# main.net
KiCad netlist of a schematic drawn in Altium Designer
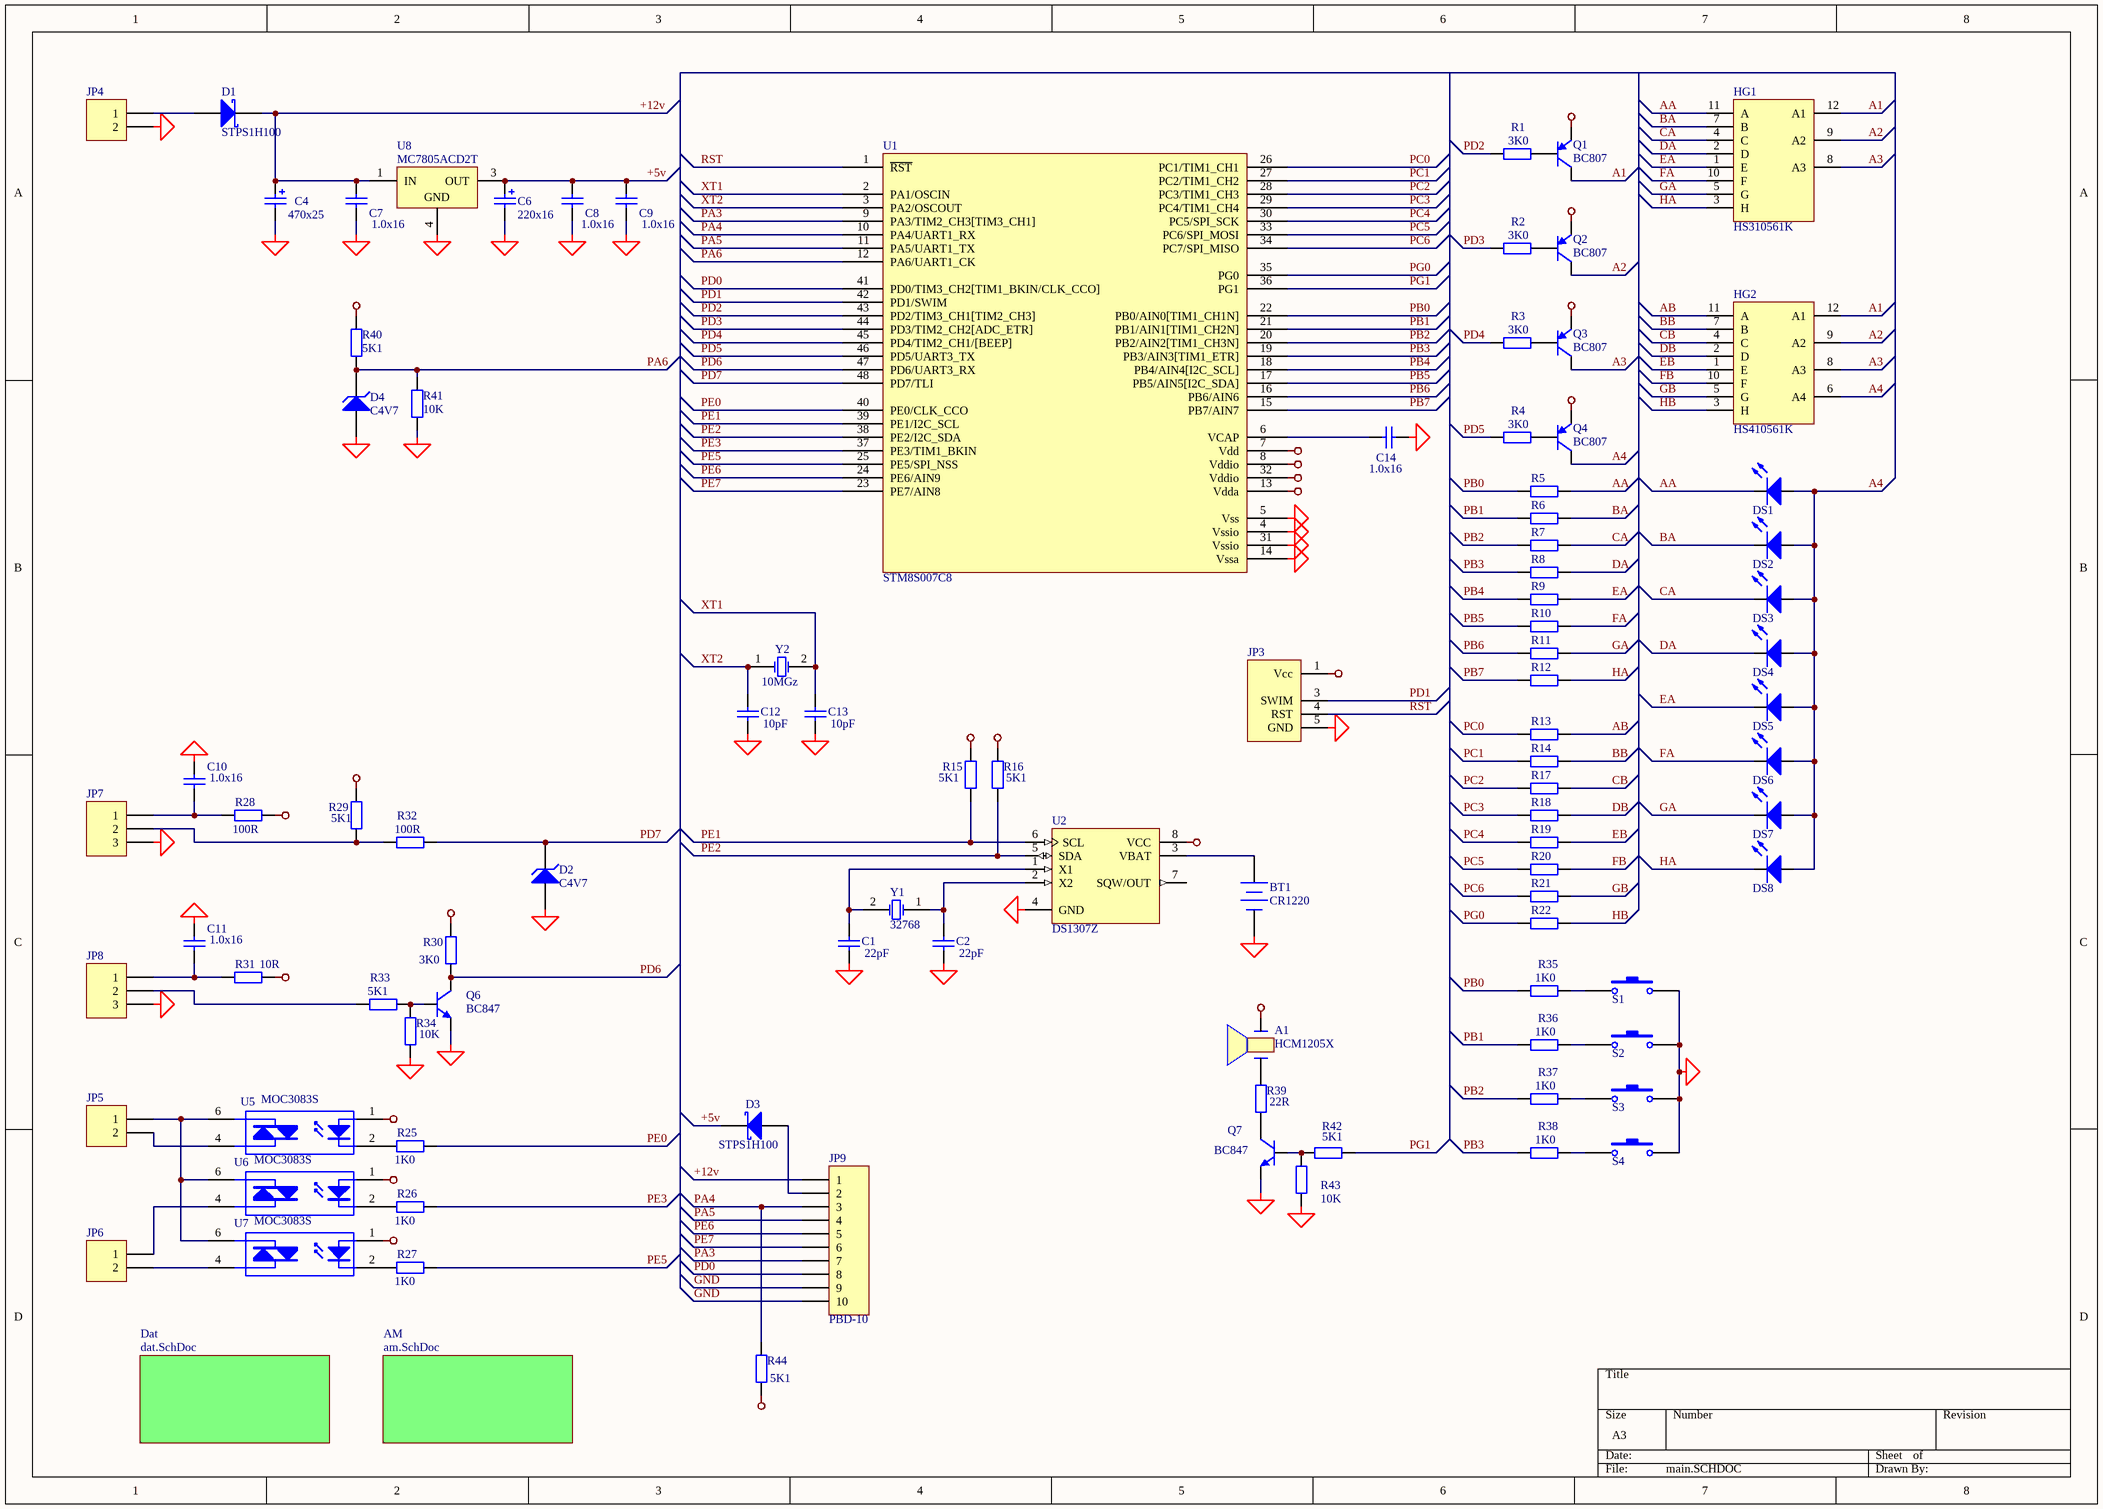
[diagram p0: main.SCHDOC]

(export (version "E")
  (design (tool "Eeschema 10.0.6"))
  (components
    (comp (ref "A1")
      (value "HCM1205X")
      (footprint "zumm")
      (description "Beeper")
      (libsource (lib "PAL") (part "PJEZ0"))
    )
    (comp (ref "BT1")
      (value "CR1220")
      (footprint "1220_holder")
      (description "Multicell Battery")
      (fields (field (name "MANUFACTURER") "Generic Components") (field (name "PUBLISHER") "Altium Limited"))
      (libsource (lib "Miscellaneous Devices") (part "Battery"))
    )
    (comp (ref "C1")
      (value "22pF")
      (footprint "_1206")
      (description "Capacitor")
      (fields (field (name "MANUFACTURER") "Generic Components") (field (name "PUBLISHER") "Altium Limited"))
      (libsource (lib "Miscellaneous Devices") (part "Cap Semi"))
    )
    (comp (ref "C2")
      (value "22pF")
      (footprint "_1206")
      (description "Capacitor")
      (fields (field (name "MANUFACTURER") "Generic Components") (field (name "PUBLISHER") "Altium Limited"))
      (libsource (lib "Miscellaneous Devices") (part "Cap Semi"))
    )
    (comp (ref "C4")
      (value "470x25")
      (footprint "el5")
      (description "Polarized Capacitor (Radial)")
      (fields (field (name "MANUFACTURER") "Generic Components") (field (name "PUBLISHER") "Altium Limited"))
      (libsource (lib "BUF") (part "Cap Pol1"))
    )
    (comp (ref "C6")
      (value "220x16")
      (footprint "el3")
      (description "Polarized Capacitor (Radial)")
      (fields (field (name "MANUFACTURER") "Generic Components") (field (name "PUBLISHER") "Altium Limited"))
      (libsource (lib "BUF") (part "Cap Pol"))
    )
    (comp (ref "C7")
      (value "1.0x16")
      (footprint "_1206")
      (description "Capacitor")
      (fields (field (name "MANUFACTURER") "Generic Components") (field (name "PUBLISHER") "Altium Limited"))
      (libsource (lib "BUF") (part "Cap"))
    )
    (comp (ref "C8")
      (value "1.0x16")
      (footprint "_1206")
      (description "Capacitor")
      (fields (field (name "MANUFACTURER") "Generic Components") (field (name "PUBLISHER") "Altium Limited"))
      (libsource (lib "BUF") (part "Cap"))
    )
    (comp (ref "C9")
      (value "1.0x16")
      (footprint "_1206")
      (description "Capacitor")
      (fields (field (name "MANUFACTURER") "Generic Components") (field (name "PUBLISHER") "Altium Limited"))
      (libsource (lib "BUF") (part "Cap"))
    )
    (comp (ref "C10")
      (value "1.0x16")
      (footprint "_1206")
      (description "Capacitor")
      (fields (field (name "MANUFACTURER") "Generic Components") (field (name "PUBLISHER") "Altium Limited"))
      (libsource (lib "BUF") (part "Cap"))
    )
    (comp (ref "C11")
      (value "1.0x16")
      (footprint "_1206")
      (description "Capacitor")
      (fields (field (name "MANUFACTURER") "Generic Components") (field (name "PUBLISHER") "Altium Limited"))
      (libsource (lib "BUF") (part "Cap"))
    )
    (comp (ref "C12")
      (value "10pF")
      (footprint "_1206")
      (description "Capacitor")
      (fields (field (name "MANUFACTURER") "Generic Components") (field (name "PUBLISHER") "Altium Limited"))
      (libsource (lib "Miscellaneous Devices") (part "Cap Semi"))
    )
    (comp (ref "C13")
      (value "10pF")
      (footprint "_1206")
      (description "Capacitor")
      (fields (field (name "MANUFACTURER") "Generic Components") (field (name "PUBLISHER") "Altium Limited"))
      (libsource (lib "Miscellaneous Devices") (part "Cap Semi"))
    )
    (comp (ref "C14")
      (value "1.0x16")
      (footprint "_1206")
      (description "Capacitor")
      (fields (field (name "MANUFACTURER") "Generic Components") (field (name "PUBLISHER") "Altium Limited"))
      (libsource (lib "Miscellaneous Devices") (part "Cap Semi"))
    )
    (comp (ref "D1")
      (value "STPS1H100")
      (footprint "mbrs140")
      (description "Schottky Rectifier")
      (fields
        (field (name "MANUFACTURER") "International Rectifier")
        (field (name "PUBLISHER") "Altium Limited")
      )
      (libsource (lib "IR Discrete Diode") (part "10BQ015"))
    )
    (comp (ref "D2")
      (value "C4V7")
      (footprint "_1206d")
      (description "Zener Diode")
      (fields (field (name "MANUFACTURER") "Generic Components") (field (name "PUBLISHER") "Altium Limited"))
      (libsource (lib "Miscellaneous Devices") (part "D Zener"))
    )
    (comp (ref "D3")
      (value "STPS1H100")
      (footprint "MBRS140")
      (description "Schottky Rectifier")
      (fields
        (field (name "MANUFACTURER") "International Rectifier")
        (field (name "PUBLISHER") "Altium Limited")
      )
      (libsource (lib "IR Discrete Diode") (part "10BQ015"))
    )
    (comp (ref "D4")
      (value "C4V7")
      (footprint "_1206d")
      (description "Zener Diode")
      (fields (field (name "MANUFACTURER") "Generic Components") (field (name "PUBLISHER") "Altium Limited"))
      (libsource (lib "Miscellaneous Devices") (part "D Zener"))
    )
    (comp (ref "DS1")
      (value "LED0")
      (footprint "el3")
      (description "Typical INFRARED GaAs LED")
      (fields (field (name "MANUFACTURER") "Generic Components") (field (name "PUBLISHER") "Altium Limited"))
      (libsource (lib "PAL") (part "LED0"))
    )
    (comp (ref "DS2")
      (value "LED0")
      (footprint "el3")
      (description "Typical INFRARED GaAs LED")
      (fields (field (name "MANUFACTURER") "Generic Components") (field (name "PUBLISHER") "Altium Limited"))
      (libsource (lib "PAL") (part "LED0"))
    )
    (comp (ref "DS3")
      (value "LED0")
      (footprint "el3")
      (description "Typical INFRARED GaAs LED")
      (fields (field (name "MANUFACTURER") "Generic Components") (field (name "PUBLISHER") "Altium Limited"))
      (libsource (lib "PAL") (part "LED0"))
    )
    (comp (ref "DS4")
      (value "LED0")
      (footprint "el3")
      (description "Typical INFRARED GaAs LED")
      (fields (field (name "MANUFACTURER") "Generic Components") (field (name "PUBLISHER") "Altium Limited"))
      (libsource (lib "PAL") (part "LED0"))
    )
    (comp (ref "DS5")
      (value "LED0")
      (footprint "el3")
      (description "Typical INFRARED GaAs LED")
      (fields (field (name "MANUFACTURER") "Generic Components") (field (name "PUBLISHER") "Altium Limited"))
      (libsource (lib "PAL") (part "LED0"))
    )
    (comp (ref "DS6")
      (value "LED0")
      (footprint "el3")
      (description "Typical INFRARED GaAs LED")
      (fields (field (name "MANUFACTURER") "Generic Components") (field (name "PUBLISHER") "Altium Limited"))
      (libsource (lib "PAL") (part "LED0"))
    )
    (comp (ref "DS7")
      (value "LED0")
      (footprint "el3")
      (description "Typical INFRARED GaAs LED")
      (fields (field (name "MANUFACTURER") "Generic Components") (field (name "PUBLISHER") "Altium Limited"))
      (libsource (lib "PAL") (part "LED0"))
    )
    (comp (ref "DS8")
      (value "LED0")
      (footprint "el3")
      (description "Typical INFRARED GaAs LED")
      (fields (field (name "MANUFACTURER") "Generic Components") (field (name "PUBLISHER") "Altium Limited"))
      (libsource (lib "PAL") (part "LED0"))
    )
    (comp (ref "HG1") (value "HS310561K") (footprint "HS310561K") (libsource (lib "PAL") (part "HS310561K")))
    (comp (ref "HG2") (value "HS410561K") (footprint "HS410561K") (libsource (lib "PAL") (part "HS410561K")))
    (comp (ref "JP3") (value "~") (footprint "HDR1X5_uart") (libsource (lib "PAL") (part "SWIM_CONN")))
    (comp (ref "JP4")
      (value "DG306-5.0-02P")
      (footprint "BT5-2")
      (description "Header, 2-Pin")
      (fields (field (name "MANUFACTURER") "Generic Components") (field (name "PUBLISHER") "Altium Limited"))
      (libsource (lib "Miscellaneous Connectors") (part "Header 2"))
    )
    (comp (ref "JP5")
      (value "DG306-5.0-02P")
      (footprint "BT5-2")
      (description "Header, 2-Pin")
      (fields (field (name "MANUFACTURER") "Generic Components") (field (name "PUBLISHER") "Altium Limited"))
      (libsource (lib "Miscellaneous Connectors") (part "Header 2"))
    )
    (comp (ref "JP6")
      (value "DG306-5.0-02P")
      (footprint "BT5-2")
      (description "Header, 2-Pin")
      (fields (field (name "MANUFACTURER") "Generic Components") (field (name "PUBLISHER") "Altium Limited"))
      (libsource (lib "Miscellaneous Connectors") (part "Header 2"))
    )
    (comp (ref "JP7")
      (value "DG306-5.0-03P")
      (footprint "BT5-3")
      (description "Header, 3-Pin")
      (fields (field (name "MANUFACTURER") "Generic Components") (field (name "PUBLISHER") "Altium Limited"))
      (libsource (lib "Miscellaneous Connectors") (part "Header 3"))
    )
    (comp (ref "JP8")
      (value "DG306-5.0-03P")
      (footprint "BT5-3")
      (description "Header, 3-Pin")
      (fields (field (name "MANUFACTURER") "Generic Components") (field (name "PUBLISHER") "Altium Limited"))
      (libsource (lib "Miscellaneous Connectors") (part "Header 3"))
    )
    (comp (ref "JP9")
      (value "PBD-10")
      (footprint "HDR2X5")
      (description "Header, 10-Pin")
      (fields (field (name "MANUFACTURER") "Generic Components") (field (name "PUBLISHER") "Altium Limited"))
      (libsource (lib "Miscellaneous Connectors") (part "Header 10"))
    )
    (comp (ref "Q1")
      (value "BC807")
      (footprint "SO-G3")
      (description "General Purpose Transistor PNP Silicon")
      (fields (field (name "MANUFACTURER") "Motorola") (field (name "PUBLISHER") "Altium Limited"))
      (libsource (lib "PAL") (part "BC857ALT1"))
    )
    (comp (ref "Q2")
      (value "BC807")
      (footprint "SO-G3")
      (description "General Purpose Transistor PNP Silicon")
      (fields (field (name "MANUFACTURER") "Motorola") (field (name "PUBLISHER") "Altium Limited"))
      (libsource (lib "PAL") (part "BC857ALT1"))
    )
    (comp (ref "Q3")
      (value "BC807")
      (footprint "SO-G3")
      (description "General Purpose Transistor PNP Silicon")
      (fields (field (name "MANUFACTURER") "Motorola") (field (name "PUBLISHER") "Altium Limited"))
      (libsource (lib "PAL") (part "BC857ALT1"))
    )
    (comp (ref "Q4")
      (value "BC807")
      (footprint "SO-G3")
      (description "General Purpose Transistor PNP Silicon")
      (fields (field (name "MANUFACTURER") "Motorola") (field (name "PUBLISHER") "Altium Limited"))
      (libsource (lib "PAL") (part "BC857ALT1"))
    )
    (comp (ref "Q6")
      (value "BC847")
      (footprint "SO-G3")
      (description "General Purpose Transistor NPN Silicon")
      (fields (field (name "MANUFACTURER") "Motorola") (field (name "PUBLISHER") "Altium Limited"))
      (libsource (lib "PAL") (part "BC847ALT1"))
    )
    (comp (ref "Q7")
      (value "BC847")
      (footprint "SO-G3")
      (description "General Purpose Transistor NPN Silicon")
      (fields (field (name "MANUFACTURER") "Motorola") (field (name "PUBLISHER") "Altium Limited"))
      (libsource (lib "PAL") (part "BC847ALT1"))
    )
    (comp (ref "R1")
      (value "3K0")
      (footprint "_1206")
      (description "Resistor")
      (fields (field (name "MANUFACTURER") "Generic Components") (field (name "PUBLISHER") "Altium Limited"))
      (libsource (lib "") (part "Res2_1"))
    )
    (comp (ref "R2")
      (value "3K0")
      (footprint "_1206")
      (description "Resistor")
      (fields (field (name "MANUFACTURER") "Generic Components") (field (name "PUBLISHER") "Altium Limited"))
      (libsource (lib "") (part "Res2_1"))
    )
    (comp (ref "R3")
      (value "3K0")
      (footprint "_1206")
      (description "Resistor")
      (fields (field (name "MANUFACTURER") "Generic Components") (field (name "PUBLISHER") "Altium Limited"))
      (libsource (lib "") (part "Res2_1"))
    )
    (comp (ref "R4")
      (value "3K0")
      (footprint "_1206")
      (description "Resistor")
      (fields (field (name "MANUFACTURER") "Generic Components") (field (name "PUBLISHER") "Altium Limited"))
      (libsource (lib "") (part "Res2_1"))
    )
    (comp (ref "R5")
      (value "100R")
      (footprint "_1206")
      (description "Resistor")
      (fields (field (name "MANUFACTURER") "Generic Components") (field (name "PUBLISHER") "Altium Limited"))
      (libsource (lib "") (part "Res2_1"))
    )
    (comp (ref "R6")
      (value "100R")
      (footprint "_1206")
      (description "Resistor")
      (fields (field (name "MANUFACTURER") "Generic Components") (field (name "PUBLISHER") "Altium Limited"))
      (libsource (lib "") (part "Res2_1"))
    )
    (comp (ref "R7")
      (value "100R")
      (footprint "_1206")
      (description "Resistor")
      (fields (field (name "MANUFACTURER") "Generic Components") (field (name "PUBLISHER") "Altium Limited"))
      (libsource (lib "") (part "Res2_1"))
    )
    (comp (ref "R8")
      (value "100R")
      (footprint "_1206")
      (description "Resistor")
      (fields (field (name "MANUFACTURER") "Generic Components") (field (name "PUBLISHER") "Altium Limited"))
      (libsource (lib "") (part "Res2_1"))
    )
    (comp (ref "R9")
      (value "100R")
      (footprint "_1206")
      (description "Resistor")
      (fields (field (name "MANUFACTURER") "Generic Components") (field (name "PUBLISHER") "Altium Limited"))
      (libsource (lib "") (part "Res2_1"))
    )
    (comp (ref "R10")
      (value "100R")
      (footprint "_1206")
      (description "Resistor")
      (fields (field (name "MANUFACTURER") "Generic Components") (field (name "PUBLISHER") "Altium Limited"))
      (libsource (lib "") (part "Res2_1"))
    )
    (comp (ref "R11")
      (value "100R")
      (footprint "_1206")
      (description "Resistor")
      (fields (field (name "MANUFACTURER") "Generic Components") (field (name "PUBLISHER") "Altium Limited"))
      (libsource (lib "") (part "Res2_1"))
    )
    (comp (ref "R12")
      (value "100R")
      (footprint "_1206")
      (description "Resistor")
      (fields (field (name "MANUFACTURER") "Generic Components") (field (name "PUBLISHER") "Altium Limited"))
      (libsource (lib "") (part "Res2_1"))
    )
    (comp (ref "R13")
      (value "100R")
      (footprint "_1206")
      (description "Resistor")
      (fields (field (name "MANUFACTURER") "Generic Components") (field (name "PUBLISHER") "Altium Limited"))
      (libsource (lib "") (part "Res2_1"))
    )
    (comp (ref "R14")
      (value "100R")
      (footprint "_1206")
      (description "Resistor")
      (fields (field (name "MANUFACTURER") "Generic Components") (field (name "PUBLISHER") "Altium Limited"))
      (libsource (lib "") (part "Res2_1"))
    )
    (comp (ref "R15")
      (value "5K1")
      (footprint "_1206")
      (description "Resistor")
      (fields (field (name "MANUFACTURER") "Generic Components") (field (name "PUBLISHER") "Altium Limited"))
      (libsource (lib "Miscellaneous Devices") (part "Res2"))
    )
    (comp (ref "R16")
      (value "5K1")
      (footprint "_1206")
      (description "Resistor")
      (fields (field (name "MANUFACTURER") "Generic Components") (field (name "PUBLISHER") "Altium Limited"))
      (libsource (lib "Miscellaneous Devices") (part "Res2"))
    )
    (comp (ref "R17")
      (value "100R")
      (footprint "_1206")
      (description "Resistor")
      (fields (field (name "MANUFACTURER") "Generic Components") (field (name "PUBLISHER") "Altium Limited"))
      (libsource (lib "") (part "Res2_1"))
    )
    (comp (ref "R18")
      (value "100R")
      (footprint "_1206")
      (description "Resistor")
      (fields (field (name "MANUFACTURER") "Generic Components") (field (name "PUBLISHER") "Altium Limited"))
      (libsource (lib "") (part "Res2_1"))
    )
    (comp (ref "R19")
      (value "100R")
      (footprint "_1206")
      (description "Resistor")
      (fields (field (name "MANUFACTURER") "Generic Components") (field (name "PUBLISHER") "Altium Limited"))
      (libsource (lib "") (part "Res2_1"))
    )
    (comp (ref "R20")
      (value "100R")
      (footprint "_1206")
      (description "Resistor")
      (fields (field (name "MANUFACTURER") "Generic Components") (field (name "PUBLISHER") "Altium Limited"))
      (libsource (lib "") (part "Res2_1"))
    )
    (comp (ref "R21")
      (value "100R")
      (footprint "_1206")
      (description "Resistor")
      (fields (field (name "MANUFACTURER") "Generic Components") (field (name "PUBLISHER") "Altium Limited"))
      (libsource (lib "") (part "Res2_1"))
    )
    (comp (ref "R22")
      (value "100R")
      (footprint "_1206")
      (description "Resistor")
      (fields (field (name "MANUFACTURER") "Generic Components") (field (name "PUBLISHER") "Altium Limited"))
      (libsource (lib "") (part "Res2_1"))
    )
    (comp (ref "R25")
      (value "1K0")
      (footprint "_1206")
      (description "Resistor")
      (fields (field (name "MANUFACTURER") "Generic Components") (field (name "PUBLISHER") "Altium Limited"))
      (libsource (lib "") (part "Res2_3"))
    )
    (comp (ref "R26")
      (value "1K0")
      (footprint "_1206")
      (description "Resistor")
      (fields (field (name "MANUFACTURER") "Generic Components") (field (name "PUBLISHER") "Altium Limited"))
      (libsource (lib "") (part "Res2_3"))
    )
    (comp (ref "R27")
      (value "1K0")
      (footprint "_1206")
      (description "Resistor")
      (fields (field (name "MANUFACTURER") "Generic Components") (field (name "PUBLISHER") "Altium Limited"))
      (libsource (lib "") (part "Res2_3"))
    )
    (comp (ref "R28")
      (value "100R")
      (footprint "_1206")
      (description "Resistor")
      (fields (field (name "MANUFACTURER") "Generic Components") (field (name "PUBLISHER") "Altium Limited"))
      (libsource (lib "") (part "Res2_3"))
    )
    (comp (ref "R29")
      (value "5K1")
      (footprint "_1206")
      (description "Resistor")
      (fields (field (name "MANUFACTURER") "Generic Components") (field (name "PUBLISHER") "Altium Limited"))
      (libsource (lib "Miscellaneous Devices") (part "Res2"))
    )
    (comp (ref "R30")
      (value "3K0")
      (footprint "_1206")
      (description "Resistor")
      (fields (field (name "MANUFACTURER") "Generic Components") (field (name "PUBLISHER") "Altium Limited"))
      (libsource (lib "Miscellaneous Devices") (part "Res2"))
    )
    (comp (ref "R31")
      (value "10R")
      (footprint "_1206")
      (description "Resistor")
      (fields (field (name "MANUFACTURER") "Generic Components") (field (name "PUBLISHER") "Altium Limited"))
      (libsource (lib "") (part "Res2_3"))
    )
    (comp (ref "R32")
      (value "100R")
      (footprint "_1206")
      (description "Resistor")
      (fields (field (name "MANUFACTURER") "Generic Components") (field (name "PUBLISHER") "Altium Limited"))
      (libsource (lib "") (part "Res2_1"))
    )
    (comp (ref "R33")
      (value "5K1")
      (footprint "_1206")
      (description "Resistor")
      (fields (field (name "MANUFACTURER") "Generic Components") (field (name "PUBLISHER") "Altium Limited"))
      (libsource (lib "") (part "Res2_1"))
    )
    (comp (ref "R34")
      (value "10K")
      (footprint "_1206")
      (description "Resistor")
      (fields (field (name "MANUFACTURER") "Generic Components") (field (name "PUBLISHER") "Altium Limited"))
      (libsource (lib "") (part "Res2_5"))
    )
    (comp (ref "R35")
      (value "1K0")
      (footprint "_1206")
      (description "Resistor")
      (fields (field (name "MANUFACTURER") "Generic Components") (field (name "PUBLISHER") "Altium Limited"))
      (libsource (lib "") (part "Res2_1"))
    )
    (comp (ref "R36")
      (value "1K0")
      (footprint "_1206")
      (description "Resistor")
      (fields (field (name "MANUFACTURER") "Generic Components") (field (name "PUBLISHER") "Altium Limited"))
      (libsource (lib "") (part "Res2_1"))
    )
    (comp (ref "R37")
      (value "1K0")
      (footprint "_1206")
      (description "Resistor")
      (fields (field (name "MANUFACTURER") "Generic Components") (field (name "PUBLISHER") "Altium Limited"))
      (libsource (lib "") (part "Res2_1"))
    )
    (comp (ref "R38")
      (value "1K0")
      (footprint "_1206")
      (description "Resistor")
      (fields (field (name "MANUFACTURER") "Generic Components") (field (name "PUBLISHER") "Altium Limited"))
      (libsource (lib "") (part "Res2_1"))
    )
    (comp (ref "R39")
      (value "22R")
      (footprint "_1206")
      (description "Resistor")
      (fields (field (name "MANUFACTURER") "Generic Components") (field (name "PUBLISHER") "Altium Limited"))
      (libsource (lib "Miscellaneous Devices") (part "Res2"))
    )
    (comp (ref "R40")
      (value "5K1")
      (footprint "_1206")
      (description "Resistor")
      (fields (field (name "MANUFACTURER") "Generic Components") (field (name "PUBLISHER") "Altium Limited"))
      (libsource (lib "Miscellaneous Devices") (part "Res2"))
    )
    (comp (ref "R41")
      (value "10K")
      (footprint "_1206")
      (description "Resistor")
      (fields (field (name "MANUFACTURER") "Generic Components") (field (name "PUBLISHER") "Altium Limited"))
      (libsource (lib "Miscellaneous Devices") (part "Res2"))
    )
    (comp (ref "R42")
      (value "5K1")
      (footprint "_1206")
      (description "Resistor")
      (fields (field (name "MANUFACTURER") "Generic Components") (field (name "PUBLISHER") "Altium Limited"))
      (libsource (lib "") (part "Res2_2"))
    )
    (comp (ref "R43")
      (value "10K")
      (footprint "_1206")
      (description "Resistor")
      (fields (field (name "MANUFACTURER") "Generic Components") (field (name "PUBLISHER") "Altium Limited"))
      (libsource (lib "") (part "Res2_1"))
    )
    (comp (ref "R44")
      (value "5K1")
      (footprint "_1206")
      (description "Resistor")
      (fields (field (name "MANUFACTURER") "Generic Components") (field (name "PUBLISHER") "Altium Limited"))
      (libsource (lib "") (part "Res2_4"))
    )
    (comp (ref "S1")
      (value "SWT-6-13mm")
      (footprint "SWT-6")
      (description "Switch")
      (fields (field (name "MANUFACTURER") "Generic Components") (field (name "PUBLISHER") "Altium Limited"))
      (libsource (lib "PAL") (part "SWT-6"))
    )
    (comp (ref "S2")
      (value "SWT-6-13mm")
      (footprint "SWT-6")
      (description "Switch")
      (fields (field (name "MANUFACTURER") "Generic Components") (field (name "PUBLISHER") "Altium Limited"))
      (libsource (lib "PAL") (part "SWT-6"))
    )
    (comp (ref "S3")
      (value "SWT-6-13mm")
      (footprint "SWT-6")
      (description "Switch")
      (fields (field (name "MANUFACTURER") "Generic Components") (field (name "PUBLISHER") "Altium Limited"))
      (libsource (lib "PAL") (part "SWT-6"))
    )
    (comp (ref "S4")
      (value "SWT-6-13mm")
      (footprint "SWT-6")
      (description "Switch")
      (fields (field (name "MANUFACTURER") "Generic Components") (field (name "PUBLISHER") "Altium Limited"))
      (libsource (lib "PAL") (part "SWT-6"))
    )
    (comp (ref "U1")
      (value "STM8S007C8")
      (footprint "F-QFP7X7-G48/X.3N")
      (libsource (lib "PAL") (part "STM8S007C8"))
    )
    (comp (ref "U2")
      (value "DS1307Z")
      (footprint "SO-G8/Z7.45")
      (description "64 X 8 Serial Real-Time Clock")
      (fields
        (field (name "MANUFACTURER") "Dallas Semiconductor")
        (field (name "PUBLISHER") "Altium Limited")
      )
      (libsource (lib "Dallas Peripheral Real Time Clock") (part "DS1307Z"))
    )
    (comp (ref "U5")
      (value "MOC3083S")
      (footprint "smdip6")
      (description "Opto-Triac")
      (fields (field (name "MANUFACTURER") "Generic Components") (field (name "PUBLISHER") "Altium Limited"))
      (libsource (lib "PAL") (part "Opto TRIAC"))
    )
    (comp (ref "U6")
      (value "MOC3083S")
      (footprint "smdip6")
      (description "Opto-Triac")
      (fields (field (name "MANUFACTURER") "Generic Components") (field (name "PUBLISHER") "Altium Limited"))
      (libsource (lib "PAL") (part "Opto TRIAC"))
    )
    (comp (ref "U7")
      (value "MOC3083S")
      (footprint "smdip6")
      (description "Opto-Triac")
      (fields (field (name "MANUFACTURER") "Generic Components") (field (name "PUBLISHER") "Altium Limited"))
      (libsource (lib "PAL") (part "Opto TRIAC"))
    )
    (comp (ref "U8")
      (value "MC7805ACD2T")
      (footprint "D2PAK")
      (description "Three-Terminal Positive Voltage Regulator")
      (fields (field (name "MANUFACTURER") "ON Semiconductor") (field (name "PUBLISHER") "Altium Limited"))
      (libsource (lib "ON Semi Power Mgt Voltage Regulator") (part "MC7805ACD2T"))
    )
    (comp (ref "Y1")
      (value "32768")
      (footprint "TMXLi-206")
      (description "Crystal Oscillator")
      (fields (field (name "MANUFACTURER") "Generic Components") (field (name "PUBLISHER") "Altium Limited"))
      (libsource (lib "Miscellaneous Devices") (part "XTAL"))
    )
    (comp (ref "Y2")
      (value "10MGz")
      (footprint "hc49/us")
      (description "Crystal Oscillator")
      (fields (field (name "MANUFACTURER") "Generic Components") (field (name "PUBLISHER") "Altium Limited"))
      (libsource (lib "Miscellaneous Devices") (part "XTAL"))
    )
  )
  (nets
    (net (code "1") (name "+5v") (class "Default")
      (node (ref "A1") (pin "1") (pinfunction "1_1") (pintype "passive"))
      (node (ref "C6") (pin "1") (pinfunction "1_1") (pintype "passive"))
      (node (ref "C8") (pin "2") (pinfunction "2_2") (pintype "passive"))
      (node (ref "C9") (pin "2") (pinfunction "2_2") (pintype "passive"))
      (node (ref "D3") (pin "2") (pinfunction "K_2") (pintype "passive"))
      (node (ref "JP3") (pin "1") (pinfunction "Vcc_1") (pintype "passive"))
      (node (ref "Q1") (pin "2") (pinfunction "E_2") (pintype "passive"))
      (node (ref "Q2") (pin "2") (pinfunction "E_2") (pintype "passive"))
      (node (ref "Q3") (pin "2") (pinfunction "E_2") (pintype "passive"))
      (node (ref "Q4") (pin "2") (pinfunction "E_2") (pintype "passive"))
      (node (ref "R15") (pin "1") (pinfunction "1_1") (pintype "passive"))
      (node (ref "R16") (pin "1") (pinfunction "1_1") (pintype "passive"))
      (node (ref "R28") (pin "2") (pinfunction "2_2") (pintype "passive"))
      (node (ref "R29") (pin "1") (pinfunction "1_1") (pintype "passive"))
      (node (ref "R30") (pin "1") (pinfunction "1_1") (pintype "passive"))
      (node (ref "R31") (pin "2") (pinfunction "2_2") (pintype "passive"))
      (node (ref "R44") (pin "1") (pinfunction "1_1") (pintype "passive"))
      (node (ref "U1") (pin "13") (pinfunction "Vdda_13") (pintype "passive"))
      (node (ref "U1") (pin "32") (pinfunction "Vddio_32") (pintype "passive"))
      (node (ref "U1") (pin "7") (pinfunction "Vdd_7") (pintype "passive"))
      (node (ref "U1") (pin "8") (pinfunction "Vddio_8") (pintype "passive"))
      (node (ref "U2") (pin "8") (pinfunction "VCC_8") (pintype "power_in"))
      (node (ref "U5") (pin "1") (pinfunction "A_1") (pintype "passive"))
      (node (ref "U6") (pin "1") (pinfunction "A_1") (pintype "passive"))
      (node (ref "U7") (pin "1") (pinfunction "A_1") (pintype "passive"))
      (node (ref "U8") (pin "3") (pinfunction "OUT_3") (pintype "power_in"))
    )
    (net (code "2") (name "+12v") (class "Default")
      (node (ref "C4") (pin "1") (pinfunction "1_1") (pintype "passive"))
      (node (ref "C7") (pin "2") (pinfunction "2_2") (pintype "passive"))
      (node (ref "D1") (pin "2") (pinfunction "K_2") (pintype "passive"))
      (node (ref "JP9") (pin "1") (pinfunction "1_1") (pintype "passive"))
      (node (ref "R40") (pin "1") (pinfunction "1_1") (pintype "passive"))
      (node (ref "U8") (pin "1") (pinfunction "IN_1") (pintype "power_in"))
    )
    (net (code "3") (name "/A1") (class "Default")
      (node (ref "HG1") (pin "12") (pinfunction "A1_12") (pintype "passive"))
      (node (ref "HG2") (pin "12") (pinfunction "A1_12") (pintype "passive"))
      (node (ref "Q1") (pin "3") (pinfunction "C_3") (pintype "passive"))
    )
    (net (code "4") (name "/A2") (class "Default")
      (node (ref "HG1") (pin "9") (pinfunction "A2_9") (pintype "passive"))
      (node (ref "HG2") (pin "9") (pinfunction "A2_9") (pintype "passive"))
      (node (ref "Q2") (pin "3") (pinfunction "C_3") (pintype "passive"))
    )
    (net (code "5") (name "/A3") (class "Default")
      (node (ref "HG1") (pin "8") (pinfunction "A3_8") (pintype "passive"))
      (node (ref "HG2") (pin "8") (pinfunction "A3_8") (pintype "passive"))
      (node (ref "Q3") (pin "3") (pinfunction "C_3") (pintype "passive"))
    )
    (net (code "6") (name "/A4") (class "Default")
      (node (ref "DS1") (pin "1") (pinfunction "A_1") (pintype "passive"))
      (node (ref "DS2") (pin "1") (pinfunction "A_1") (pintype "passive"))
      (node (ref "DS3") (pin "1") (pinfunction "A_1") (pintype "passive"))
      (node (ref "DS4") (pin "1") (pinfunction "A_1") (pintype "passive"))
      (node (ref "DS5") (pin "1") (pinfunction "A_1") (pintype "passive"))
      (node (ref "DS6") (pin "1") (pinfunction "A_1") (pintype "passive"))
      (node (ref "DS7") (pin "1") (pinfunction "A_1") (pintype "passive"))
      (node (ref "DS8") (pin "1") (pinfunction "A_1") (pintype "passive"))
      (node (ref "HG2") (pin "6") (pinfunction "A4_6") (pintype "passive"))
      (node (ref "Q4") (pin "3") (pinfunction "C_3") (pintype "passive"))
    )
    (net (code "7") (name "/AA") (class "Default")
      (node (ref "DS1") (pin "2") (pinfunction "K_2") (pintype "passive"))
      (node (ref "HG1") (pin "11") (pinfunction "A_11") (pintype "passive"))
      (node (ref "R5") (pin "1") (pinfunction "1_1") (pintype "passive"))
    )
    (net (code "8") (name "/AB") (class "Default")
      (node (ref "HG2") (pin "11") (pinfunction "A_11") (pintype "passive"))
      (node (ref "R13") (pin "1") (pinfunction "1_1") (pintype "passive"))
    )
    (net (code "9") (name "/BA") (class "Default")
      (node (ref "DS2") (pin "2") (pinfunction "K_2") (pintype "passive"))
      (node (ref "HG1") (pin "7") (pinfunction "B_7") (pintype "passive"))
      (node (ref "R6") (pin "1") (pinfunction "1_1") (pintype "passive"))
    )
    (net (code "10") (name "/BB") (class "Default")
      (node (ref "HG2") (pin "7") (pinfunction "B_7") (pintype "passive"))
      (node (ref "R14") (pin "1") (pinfunction "1_1") (pintype "passive"))
    )
    (net (code "11") (name "/CA") (class "Default")
      (node (ref "DS3") (pin "2") (pinfunction "K_2") (pintype "passive"))
      (node (ref "HG1") (pin "4") (pinfunction "C_4") (pintype "passive"))
      (node (ref "R7") (pin "1") (pinfunction "1_1") (pintype "passive"))
    )
    (net (code "12") (name "/CB") (class "Default")
      (node (ref "HG2") (pin "4") (pinfunction "C_4") (pintype "passive"))
      (node (ref "R17") (pin "1") (pinfunction "1_1") (pintype "passive"))
    )
    (net (code "13") (name "/DA") (class "Default")
      (node (ref "DS4") (pin "2") (pinfunction "K_2") (pintype "passive"))
      (node (ref "HG1") (pin "2") (pinfunction "D_2") (pintype "passive"))
      (node (ref "R8") (pin "1") (pinfunction "1_1") (pintype "passive"))
    )
    (net (code "14") (name "/DB") (class "Default")
      (node (ref "HG2") (pin "2") (pinfunction "D_2") (pintype "passive"))
      (node (ref "R18") (pin "1") (pinfunction "1_1") (pintype "passive"))
    )
    (net (code "15") (name "/EA") (class "Default")
      (node (ref "DS5") (pin "2") (pinfunction "K_2") (pintype "passive"))
      (node (ref "HG1") (pin "1") (pinfunction "E_1") (pintype "passive"))
      (node (ref "R9") (pin "1") (pinfunction "1_1") (pintype "passive"))
    )
    (net (code "16") (name "/EB") (class "Default")
      (node (ref "HG2") (pin "1") (pinfunction "E_1") (pintype "passive"))
      (node (ref "R19") (pin "1") (pinfunction "1_1") (pintype "passive"))
    )
    (net (code "17") (name "/FA") (class "Default")
      (node (ref "DS6") (pin "2") (pinfunction "K_2") (pintype "passive"))
      (node (ref "HG1") (pin "10") (pinfunction "F_10") (pintype "passive"))
      (node (ref "R10") (pin "1") (pinfunction "1_1") (pintype "passive"))
    )
    (net (code "18") (name "/FB") (class "Default")
      (node (ref "HG2") (pin "10") (pinfunction "F_10") (pintype "passive"))
      (node (ref "R20") (pin "1") (pinfunction "1_1") (pintype "passive"))
    )
    (net (code "19") (name "/GA") (class "Default")
      (node (ref "DS7") (pin "2") (pinfunction "K_2") (pintype "passive"))
      (node (ref "HG1") (pin "5") (pinfunction "G_5") (pintype "passive"))
      (node (ref "R11") (pin "1") (pinfunction "1_1") (pintype "passive"))
    )
    (net (code "20") (name "/GB") (class "Default")
      (node (ref "HG2") (pin "5") (pinfunction "G_5") (pintype "passive"))
      (node (ref "R21") (pin "1") (pinfunction "1_1") (pintype "passive"))
    )
    (net (code "21") (name "/HA") (class "Default")
      (node (ref "DS8") (pin "2") (pinfunction "K_2") (pintype "passive"))
      (node (ref "HG1") (pin "3") (pinfunction "H_3") (pintype "passive"))
      (node (ref "R12") (pin "1") (pinfunction "1_1") (pintype "passive"))
    )
    (net (code "22") (name "/HB") (class "Default")
      (node (ref "HG2") (pin "3") (pinfunction "H_3") (pintype "passive"))
      (node (ref "R22") (pin "1") (pinfunction "1_1") (pintype "passive"))
    )
    (net (code "23") (name "/PA3") (class "Default")
      (node (ref "JP9") (pin "7") (pinfunction "7_7") (pintype "passive"))
      (node (ref "U1") (pin "9") (pinfunction "PA3/TIM2_CH3[TIM3_CH1]_9") (pintype "passive"))
    )
    (net (code "24") (name "/PA4") (class "Default")
      (node (ref "JP9") (pin "3") (pinfunction "3_3") (pintype "passive"))
      (node (ref "R44") (pin "2") (pinfunction "2_2") (pintype "passive"))
      (node (ref "U1") (pin "10") (pinfunction "PA4/UART1_RX_10") (pintype "passive"))
    )
    (net (code "25") (name "/PA5") (class "Default")
      (node (ref "JP9") (pin "4") (pinfunction "4_4") (pintype "passive"))
      (node (ref "U1") (pin "11") (pinfunction "PA5/UART1_TX_11") (pintype "passive"))
    )
    (net (code "26") (name "/PA6") (class "Default")
      (node (ref "D4") (pin "2") (pinfunction "K_2") (pintype "passive"))
      (node (ref "R40") (pin "2") (pinfunction "2_2") (pintype "passive"))
      (node (ref "R41") (pin "1") (pinfunction "1_1") (pintype "passive"))
      (node (ref "U1") (pin "12") (pinfunction "PA6/UART1_CK_12") (pintype "passive"))
    )
    (net (code "27") (name "/PB0") (class "Default")
      (node (ref "R35") (pin "2") (pinfunction "2_2") (pintype "passive"))
      (node (ref "R5") (pin "2") (pinfunction "2_2") (pintype "passive"))
      (node (ref "U1") (pin "22") (pinfunction "PB0/AIN0[TIM1_CH1N]_22") (pintype "passive"))
    )
    (net (code "28") (name "/PB1") (class "Default")
      (node (ref "R36") (pin "2") (pinfunction "2_2") (pintype "passive"))
      (node (ref "R6") (pin "2") (pinfunction "2_2") (pintype "passive"))
      (node (ref "U1") (pin "21") (pinfunction "PB1/AIN1[TIM1_CH2N]_21") (pintype "passive"))
    )
    (net (code "29") (name "/PB2") (class "Default")
      (node (ref "R37") (pin "2") (pinfunction "2_2") (pintype "passive"))
      (node (ref "R7") (pin "2") (pinfunction "2_2") (pintype "passive"))
      (node (ref "U1") (pin "20") (pinfunction "PB2/AIN2[TIM1_CH3N]_20") (pintype "passive"))
    )
    (net (code "30") (name "/PB3") (class "Default")
      (node (ref "R38") (pin "2") (pinfunction "2_2") (pintype "passive"))
      (node (ref "R8") (pin "2") (pinfunction "2_2") (pintype "passive"))
      (node (ref "U1") (pin "19") (pinfunction "PB3/AIN3[TIM1_ETR]_19") (pintype "passive"))
    )
    (net (code "31") (name "/PB4") (class "Default")
      (node (ref "R9") (pin "2") (pinfunction "2_2") (pintype "passive"))
      (node (ref "U1") (pin "18") (pinfunction "PB4/AIN4[I2C_SCL]_18") (pintype "passive"))
    )
    (net (code "32") (name "/PB5") (class "Default")
      (node (ref "R10") (pin "2") (pinfunction "2_2") (pintype "passive"))
      (node (ref "U1") (pin "17") (pinfunction "PB5/AIN5[I2C_SDA]_17") (pintype "passive"))
    )
    (net (code "33") (name "/PB6") (class "Default")
      (node (ref "R11") (pin "2") (pinfunction "2_2") (pintype "passive"))
      (node (ref "U1") (pin "16") (pinfunction "PB6/AIN6_16") (pintype "passive"))
    )
    (net (code "34") (name "/PB7") (class "Default")
      (node (ref "R12") (pin "2") (pinfunction "2_2") (pintype "passive"))
      (node (ref "U1") (pin "15") (pinfunction "PB7/AIN7_15") (pintype "passive"))
    )
    (net (code "35") (name "/PC0") (class "Default")
      (node (ref "R13") (pin "2") (pinfunction "2_2") (pintype "passive"))
      (node (ref "U1") (pin "26") (pinfunction "PC1/TIM1_CH1_26") (pintype "passive"))
    )
    (net (code "36") (name "/PC1") (class "Default")
      (node (ref "R14") (pin "2") (pinfunction "2_2") (pintype "passive"))
      (node (ref "U1") (pin "27") (pinfunction "PC2/TIM1_CH2_27") (pintype "passive"))
    )
    (net (code "37") (name "/PC2") (class "Default")
      (node (ref "R17") (pin "2") (pinfunction "2_2") (pintype "passive"))
      (node (ref "U1") (pin "28") (pinfunction "PC3/TIM1_CH3_28") (pintype "passive"))
    )
    (net (code "38") (name "/PC3") (class "Default")
      (node (ref "R18") (pin "2") (pinfunction "2_2") (pintype "passive"))
      (node (ref "U1") (pin "29") (pinfunction "PC4/TIM1_CH4_29") (pintype "passive"))
    )
    (net (code "39") (name "/PC4") (class "Default")
      (node (ref "R19") (pin "2") (pinfunction "2_2") (pintype "passive"))
      (node (ref "U1") (pin "30") (pinfunction "PC5/SPI_SCK_30") (pintype "passive"))
    )
    (net (code "40") (name "/PC5") (class "Default")
      (node (ref "R20") (pin "2") (pinfunction "2_2") (pintype "passive"))
      (node (ref "U1") (pin "33") (pinfunction "PC6/SPI_MOSI_33") (pintype "passive"))
    )
    (net (code "41") (name "/PC6") (class "Default")
      (node (ref "R21") (pin "2") (pinfunction "2_2") (pintype "passive"))
      (node (ref "U1") (pin "34") (pinfunction "PC7/SPI_MISO_34") (pintype "passive"))
    )
    (net (code "42") (name "/PD0") (class "Default")
      (node (ref "JP9") (pin "8") (pinfunction "8_8") (pintype "passive"))
      (node (ref "U1") (pin "41") (pinfunction "PD0/TIM3_CH2[TIM1_BKIN/CLK_CCO]_41") (pintype "passive"))
    )
    (net (code "43") (name "/PD1") (class "Default")
      (node (ref "JP3") (pin "3") (pinfunction "SWIM_3") (pintype "passive"))
      (node (ref "U1") (pin "42") (pinfunction "PD1/SWIM_42") (pintype "passive"))
    )
    (net (code "44") (name "/PD2") (class "Default")
      (node (ref "R1") (pin "2") (pinfunction "2_2") (pintype "passive"))
      (node (ref "U1") (pin "43") (pinfunction "PD2/TIM3_CH1[TIM2_CH3]_43") (pintype "passive"))
    )
    (net (code "45") (name "/PD3") (class "Default")
      (node (ref "R2") (pin "2") (pinfunction "2_2") (pintype "passive"))
      (node (ref "U1") (pin "44") (pinfunction "PD3/TIM2_CH2[ADC_ETR]_44") (pintype "passive"))
    )
    (net (code "46") (name "/PD4") (class "Default")
      (node (ref "R3") (pin "2") (pinfunction "2_2") (pintype "passive"))
      (node (ref "U1") (pin "45") (pinfunction "PD4/TIM2_CH1/[BEEP]_45") (pintype "passive"))
    )
    (net (code "47") (name "/PD5") (class "Default")
      (node (ref "R4") (pin "2") (pinfunction "2_2") (pintype "passive"))
      (node (ref "U1") (pin "46") (pinfunction "PD5/UART3_TX_46") (pintype "passive"))
    )
    (net (code "48") (name "/PD6") (class "Default")
      (node (ref "Q6") (pin "3") (pinfunction "C_3") (pintype "passive"))
      (node (ref "R30") (pin "2") (pinfunction "2_2") (pintype "passive"))
      (node (ref "U1") (pin "47") (pinfunction "PD6/UART3_RX_47") (pintype "passive"))
    )
    (net (code "49") (name "/PD7") (class "Default")
      (node (ref "D2") (pin "2") (pinfunction "K_2") (pintype "passive"))
      (node (ref "R32") (pin "1") (pinfunction "1_1") (pintype "passive"))
      (node (ref "U1") (pin "48") (pinfunction "PD7/TLI_48") (pintype "passive"))
    )
    (net (code "50") (name "/PE0") (class "Default")
      (node (ref "R25") (pin "2") (pinfunction "2_2") (pintype "passive"))
      (node (ref "U1") (pin "40") (pinfunction "PE0/CLK_CCO_40") (pintype "passive"))
    )
    (net (code "51") (name "/PE1") (class "Default")
      (node (ref "R15") (pin "2") (pinfunction "2_2") (pintype "passive"))
      (node (ref "U1") (pin "39") (pinfunction "PE1/I2C_SCL_39") (pintype "passive"))
      (node (ref "U2") (pin "6") (pinfunction "SCL_6") (pintype "input"))
    )
    (net (code "52") (name "/PE2") (class "Default")
      (node (ref "R16") (pin "2") (pinfunction "2_2") (pintype "passive"))
      (node (ref "U1") (pin "38") (pinfunction "PE2/I2C_SDA_38") (pintype "passive"))
      (node (ref "U2") (pin "5") (pinfunction "SDA_5") (pintype "bidirectional"))
    )
    (net (code "53") (name "/PE3") (class "Default")
      (node (ref "R26") (pin "2") (pinfunction "2_2") (pintype "passive"))
      (node (ref "U1") (pin "37") (pinfunction "PE3/TIM1_BKIN_37") (pintype "passive"))
    )
    (net (code "54") (name "/PE5") (class "Default")
      (node (ref "R27") (pin "2") (pinfunction "2_2") (pintype "passive"))
      (node (ref "U1") (pin "25") (pinfunction "PE5/SPI_NSS_25") (pintype "passive"))
    )
    (net (code "55") (name "/PE6") (class "Default")
      (node (ref "JP9") (pin "5") (pinfunction "5_5") (pintype "passive"))
      (node (ref "U1") (pin "24") (pinfunction "PE6/AIN9_24") (pintype "passive"))
    )
    (net (code "56") (name "/PE7") (class "Default")
      (node (ref "JP9") (pin "6") (pinfunction "6_6") (pintype "passive"))
      (node (ref "U1") (pin "23") (pinfunction "PE7/AIN8_23") (pintype "passive"))
    )
    (net (code "57") (name "/PG0") (class "Default")
      (node (ref "R22") (pin "2") (pinfunction "2_2") (pintype "passive"))
      (node (ref "U1") (pin "35") (pinfunction "PG0_35") (pintype "passive"))
    )
    (net (code "58") (name "/PG1") (class "Default")
      (node (ref "R42") (pin "2") (pinfunction "2_2") (pintype "passive"))
      (node (ref "U1") (pin "36") (pinfunction "PG1_36") (pintype "passive"))
    )
    (net (code "59") (name "/RST") (class "Default")
      (node (ref "JP3") (pin "4") (pinfunction "RST_4") (pintype "passive"))
      (node (ref "U1") (pin "1") (pinfunction "~{RST}_1") (pintype "passive"))
    )
    (net (code "60") (name "/XT1") (class "Default")
      (node (ref "C13") (pin "2") (pinfunction "2_2") (pintype "passive"))
      (node (ref "U1") (pin "2") (pinfunction "PA1/OSCIN_2") (pintype "passive"))
      (node (ref "Y2") (pin "2") (pinfunction "OSC2_2") (pintype "passive"))
    )
    (net (code "61") (name "/XT2") (class "Default")
      (node (ref "C12") (pin "2") (pinfunction "2_2") (pintype "passive"))
      (node (ref "U1") (pin "3") (pinfunction "PA2/OSCOUT_3") (pintype "passive"))
      (node (ref "Y2") (pin "1") (pinfunction "OSC1_1") (pintype "passive"))
    )
    (net (code "62") (name "GND") (class "Default")
      (node (ref "BT1") (pin "2") (pinfunction "-_2") (pintype "passive"))
      (node (ref "C1") (pin "1") (pinfunction "1_1") (pintype "passive"))
      (node (ref "C10") (pin "2") (pinfunction "2_2") (pintype "passive"))
      (node (ref "C11") (pin "2") (pinfunction "2_2") (pintype "passive"))
      (node (ref "C12") (pin "1") (pinfunction "1_1") (pintype "passive"))
      (node (ref "C13") (pin "1") (pinfunction "1_1") (pintype "passive"))
      (node (ref "C14") (pin "1") (pinfunction "1_1") (pintype "passive"))
      (node (ref "C2") (pin "1") (pinfunction "1_1") (pintype "passive"))
      (node (ref "C4") (pin "2") (pinfunction "2_2") (pintype "passive"))
      (node (ref "C6") (pin "2") (pinfunction "2_2") (pintype "passive"))
      (node (ref "C7") (pin "1") (pinfunction "1_1") (pintype "passive"))
      (node (ref "C8") (pin "1") (pinfunction "1_1") (pintype "passive"))
      (node (ref "C9") (pin "1") (pinfunction "1_1") (pintype "passive"))
      (node (ref "D2") (pin "1") (pinfunction "A_1") (pintype "passive"))
      (node (ref "D4") (pin "1") (pinfunction "A_1") (pintype "passive"))
      (node (ref "JP3") (pin "5") (pinfunction "GND_5") (pintype "passive"))
      (node (ref "JP4") (pin "2") (pinfunction "2_2") (pintype "passive"))
      (node (ref "JP7") (pin "3") (pinfunction "3_3") (pintype "passive"))
      (node (ref "JP8") (pin "3") (pinfunction "3_3") (pintype "passive"))
      (node (ref "JP9") (pin "10") (pinfunction "10_10") (pintype "passive"))
      (node (ref "JP9") (pin "9") (pinfunction "9_9") (pintype "passive"))
      (node (ref "Q6") (pin "2") (pinfunction "E_2") (pintype "passive"))
      (node (ref "Q7") (pin "2") (pinfunction "E_2") (pintype "passive"))
      (node (ref "R34") (pin "2") (pinfunction "2_2") (pintype "passive"))
      (node (ref "R41") (pin "2") (pinfunction "2_2") (pintype "passive"))
      (node (ref "R43") (pin "2") (pinfunction "2_2") (pintype "passive"))
      (node (ref "S1") (pin "2") (pinfunction "2_2") (pintype "passive"))
      (node (ref "S2") (pin "2") (pinfunction "2_2") (pintype "passive"))
      (node (ref "S3") (pin "2") (pinfunction "2_2") (pintype "passive"))
      (node (ref "S4") (pin "2") (pinfunction "2_2") (pintype "passive"))
      (node (ref "U1") (pin "14") (pinfunction "Vssa_14") (pintype "passive"))
      (node (ref "U1") (pin "31") (pinfunction "Vssio_31") (pintype "passive"))
      (node (ref "U1") (pin "4") (pinfunction "Vssio_4") (pintype "passive"))
      (node (ref "U1") (pin "5") (pinfunction "Vss_5") (pintype "passive"))
      (node (ref "U2") (pin "4") (pinfunction "GND_4") (pintype "power_in"))
      (node (ref "U8") (pin "4") (pinfunction "GND_4") (pintype "power_in"))
    )
    (net (code "63") (name "Net-(A1-Pad2)") (class "Default")
      (node (ref "A1") (pin "2") (pinfunction "2_2") (pintype "passive"))
      (node (ref "R39") (pin "1") (pinfunction "1_1") (pintype "passive"))
    )
    (net (code "64") (name "Net-(BT1-+)") (class "Default")
      (node (ref "BT1") (pin "1") (pinfunction "+_1") (pintype "passive"))
      (node (ref "U2") (pin "3") (pinfunction "VBAT_3") (pintype "power_in"))
    )
    (net (code "65") (name "Net-(C10-Pad1)") (class "Default")
      (node (ref "C10") (pin "1") (pinfunction "1_1") (pintype "passive"))
      (node (ref "JP7") (pin "1") (pinfunction "1_1") (pintype "passive"))
      (node (ref "R28") (pin "1") (pinfunction "1_1") (pintype "passive"))
    )
    (net (code "66") (name "Net-(C11-Pad1)") (class "Default")
      (node (ref "C11") (pin "1") (pinfunction "1_1") (pintype "passive"))
      (node (ref "JP8") (pin "1") (pinfunction "1_1") (pintype "passive"))
      (node (ref "R31") (pin "1") (pinfunction "1_1") (pintype "passive"))
    )
    (net (code "67") (name "Net-(D1-A)") (class "Default")
      (node (ref "D1") (pin "1") (pinfunction "A_1") (pintype "passive"))
      (node (ref "JP4") (pin "1") (pinfunction "1_1") (pintype "passive"))
    )
    (net (code "68") (name "Net-(D3-A)") (class "Default")
      (node (ref "D3") (pin "1") (pinfunction "A_1") (pintype "passive"))
      (node (ref "JP9") (pin "2") (pinfunction "2_2") (pintype "passive"))
    )
    (net (code "69") (name "Net-(JP5-Pad1)") (class "Default")
      (node (ref "JP5") (pin "1") (pinfunction "1_1") (pintype "passive"))
      (node (ref "U5") (pin "6") (pinfunction "A/K_6") (pintype "passive"))
      (node (ref "U6") (pin "6") (pinfunction "A/K_6") (pintype "passive"))
      (node (ref "U7") (pin "6") (pinfunction "A/K_6") (pintype "passive"))
    )
    (net (code "70") (name "Net-(JP5-Pad2)") (class "Default")
      (node (ref "JP5") (pin "2") (pinfunction "2_2") (pintype "passive"))
      (node (ref "U5") (pin "4") (pinfunction "A/K_4") (pintype "passive"))
    )
    (net (code "71") (name "Net-(JP6-Pad1)") (class "Default")
      (node (ref "JP6") (pin "1") (pinfunction "1_1") (pintype "passive"))
      (node (ref "U6") (pin "4") (pinfunction "A/K_4") (pintype "passive"))
    )
    (net (code "72") (name "Net-(JP6-Pad2)") (class "Default")
      (node (ref "JP6") (pin "2") (pinfunction "2_2") (pintype "passive"))
      (node (ref "U7") (pin "4") (pinfunction "A/K_4") (pintype "passive"))
    )
    (net (code "73") (name "Net-(JP7-Pad2)") (class "Default")
      (node (ref "JP7") (pin "2") (pinfunction "2_2") (pintype "passive"))
      (node (ref "R29") (pin "2") (pinfunction "2_2") (pintype "passive"))
      (node (ref "R32") (pin "2") (pinfunction "2_2") (pintype "passive"))
    )
    (net (code "74") (name "Net-(JP8-Pad2)") (class "Default")
      (node (ref "JP8") (pin "2") (pinfunction "2_2") (pintype "passive"))
      (node (ref "R33") (pin "2") (pinfunction "2_2") (pintype "passive"))
    )
    (net (code "75") (name "Net-(Q1-B)") (class "Default")
      (node (ref "Q1") (pin "1") (pinfunction "B_1") (pintype "passive"))
      (node (ref "R1") (pin "1") (pinfunction "1_1") (pintype "passive"))
    )
    (net (code "76") (name "Net-(Q2-B)") (class "Default")
      (node (ref "Q2") (pin "1") (pinfunction "B_1") (pintype "passive"))
      (node (ref "R2") (pin "1") (pinfunction "1_1") (pintype "passive"))
    )
    (net (code "77") (name "Net-(Q3-B)") (class "Default")
      (node (ref "Q3") (pin "1") (pinfunction "B_1") (pintype "passive"))
      (node (ref "R3") (pin "1") (pinfunction "1_1") (pintype "passive"))
    )
    (net (code "78") (name "Net-(Q4-B)") (class "Default")
      (node (ref "Q4") (pin "1") (pinfunction "B_1") (pintype "passive"))
      (node (ref "R4") (pin "1") (pinfunction "1_1") (pintype "passive"))
    )
    (net (code "79") (name "Net-(Q6-B)") (class "Default")
      (node (ref "Q6") (pin "1") (pinfunction "B_1") (pintype "passive"))
      (node (ref "R33") (pin "1") (pinfunction "1_1") (pintype "passive"))
      (node (ref "R34") (pin "1") (pinfunction "1_1") (pintype "passive"))
    )
    (net (code "80") (name "Net-(Q7-B)") (class "Default")
      (node (ref "Q7") (pin "1") (pinfunction "B_1") (pintype "passive"))
      (node (ref "R42") (pin "1") (pinfunction "1_1") (pintype "passive"))
      (node (ref "R43") (pin "1") (pinfunction "1_1") (pintype "passive"))
    )
    (net (code "81") (name "Net-(Q7-C)") (class "Default")
      (node (ref "Q7") (pin "3") (pinfunction "C_3") (pintype "passive"))
      (node (ref "R39") (pin "2") (pinfunction "2_2") (pintype "passive"))
    )
    (net (code "82") (name "Net-(R35-Pad1)") (class "Default")
      (node (ref "R35") (pin "1") (pinfunction "1_1") (pintype "passive"))
      (node (ref "S1") (pin "1") (pinfunction "1_1") (pintype "passive"))
    )
    (net (code "83") (name "Net-(R36-Pad1)") (class "Default")
      (node (ref "R36") (pin "1") (pinfunction "1_1") (pintype "passive"))
      (node (ref "S2") (pin "1") (pinfunction "1_1") (pintype "passive"))
    )
    (net (code "84") (name "Net-(R37-Pad1)") (class "Default")
      (node (ref "R37") (pin "1") (pinfunction "1_1") (pintype "passive"))
      (node (ref "S3") (pin "1") (pinfunction "1_1") (pintype "passive"))
    )
    (net (code "85") (name "Net-(R38-Pad1)") (class "Default")
      (node (ref "R38") (pin "1") (pinfunction "1_1") (pintype "passive"))
      (node (ref "S4") (pin "1") (pinfunction "1_1") (pintype "passive"))
    )
    (net (code "86") (name "Net-(U1-VCAP)") (class "Default")
      (node (ref "C14") (pin "2") (pinfunction "2_2") (pintype "passive"))
      (node (ref "U1") (pin "6") (pinfunction "VCAP_6") (pintype "passive"))
    )
    (net (code "87") (name "Net-(U2-X1)") (class "Default")
      (node (ref "C1") (pin "2") (pinfunction "2_2") (pintype "passive"))
      (node (ref "U2") (pin "1") (pinfunction "X1_1") (pintype "input"))
      (node (ref "Y1") (pin "2") (pinfunction "OSC2_2") (pintype "passive"))
    )
    (net (code "88") (name "Net-(U2-X2)") (class "Default")
      (node (ref "C2") (pin "2") (pinfunction "2_2") (pintype "passive"))
      (node (ref "U2") (pin "2") (pinfunction "X2_2") (pintype "input"))
      (node (ref "Y1") (pin "1") (pinfunction "OSC1_1") (pintype "passive"))
    )
    (net (code "89") (name "Net-(U5-K)") (class "Default")
      (node (ref "R25") (pin "1") (pinfunction "1_1") (pintype "passive"))
      (node (ref "U5") (pin "2") (pinfunction "K_2") (pintype "passive"))
    )
    (net (code "90") (name "Net-(U6-K)") (class "Default")
      (node (ref "R26") (pin "1") (pinfunction "1_1") (pintype "passive"))
      (node (ref "U6") (pin "2") (pinfunction "K_2") (pintype "passive"))
    )
    (net (code "91") (name "Net-(U7-K)") (class "Default")
      (node (ref "R27") (pin "1") (pinfunction "1_1") (pintype "passive"))
      (node (ref "U7") (pin "2") (pinfunction "K_2") (pintype "passive"))
    )
    (net (code "92") (name "unconnected-(U2-SQW{slash}OUT-Pad7)") (class "Default")
      (node (ref "U2") (pin "7") (pinfunction "SQW/OUT_7") (pintype "output"))
    )
  )
)
